# smart-car-main-board.net
KiCad netlist of a schematic drawn in EasyEDA Pro
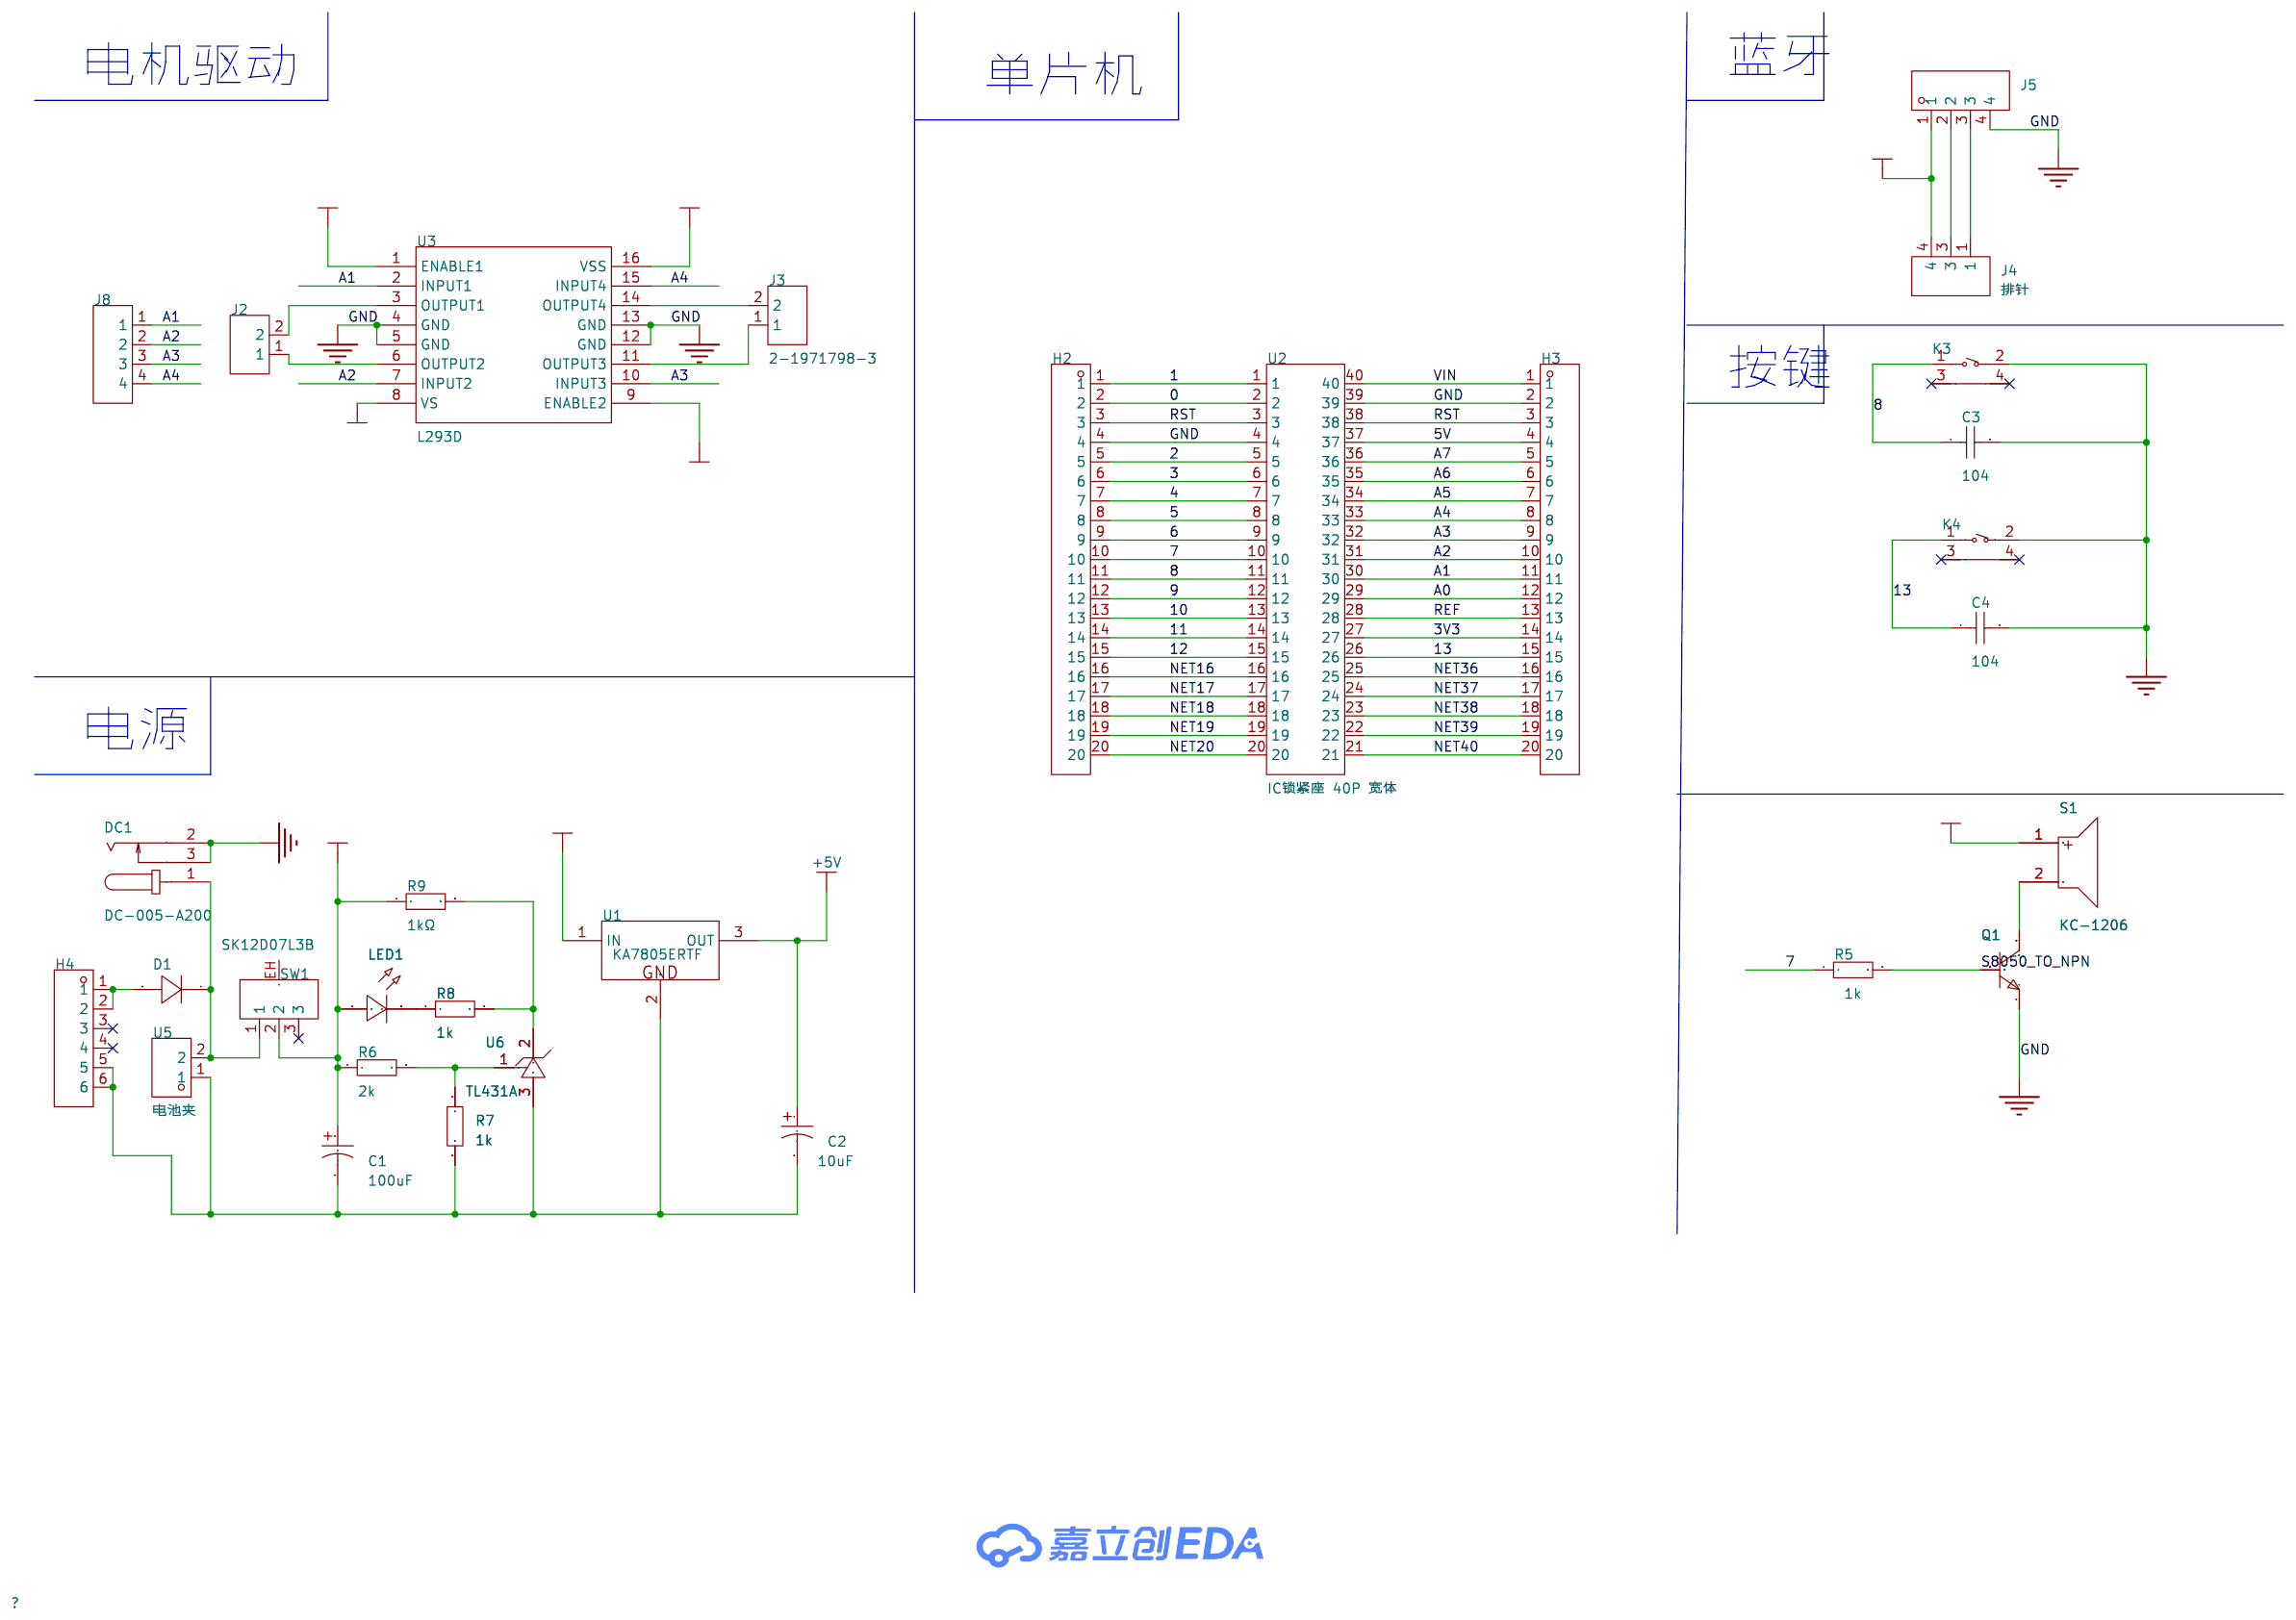
[diagram p0: schematic sheet]

(export (version "E")
  (design (tool "Eeschema 10.0.6"))
  (components
    (comp (ref "C1") (value "100uF") (libsource (lib "easyedapro") (part "CAP POL1")))
    (comp (ref "C2") (value "10uF") (libsource (lib "easyedapro") (part "CAP POL1")))
    (comp (ref "C3") (value "104") (libsource (lib "easyedapro") (part "CAP")))
    (comp (ref "C4") (value "104") (libsource (lib "easyedapro") (part "CAP")))
    (comp (ref "D1")
      (value "~")
      (footprint "easyedapro:DO_1N4007")
      (libsource (lib "easyedapro") (part "D_1N4007"))
    )
    (comp (ref "DC1")
      (value "DC-005-A200")
      (footprint "easyedapro:DC-IN-TH_DC-005-A200")
      (description "连接器类型:DC电源插座;安装方式:弯插;触点内径:2mm;触点外径:6.4mm;额定电流:3A;额定电压:30V;工作温度:-20°C~+70°C;")
      (fields (field (name "Manufacturer") "XUNPU(讯普)"))
      (libsource (lib "easyedapro") (part "DC-005-A200"))
    )
    (comp (ref "H2")
      (value "~")
      (footprint "easyedapro:HDR-TH_20P-P2.54-V-M-1")
      (libsource (lib "easyedapro") (part "HDR_2.54-1x20P"))
    )
    (comp (ref "H3")
      (value "~")
      (footprint "easyedapro:HDR-TH_20P-P2.54-V-M-1")
      (libsource (lib "easyedapro") (part "HDR_2.54-1x20P"))
    )
    (comp (ref "H4")
      (value "~")
      (footprint "easyedapro:HDR-TH_6P-P2.54-V-F")
      (libsource (lib "easyedapro") (part "Header-Female-2.54_1x6"))
    )
    (comp (ref "J2")
      (value "2-1971798-3")
      (footprint "easyedapro:CONN-TH_2-1971798-3")
      (libsource (lib "easyedapro") (part "2-1971798-3"))
    )
    (comp (ref "J3")
      (value "2-1971798-3")
      (footprint "easyedapro:CONN-TH_2-1971798-3")
      (libsource (lib "easyedapro") (part "2-1971798-3"))
    )
    (comp (ref "J4")
      (value "排针")
      (footprint "easyedapro:HDR-TH_3P-P2.54-V-M_H254-1X3P")
      (libsource (lib "easyedapro") (part "H254-1X4P-P2NC-PA4-PS5-PB8-L17MM"))
    )
    (comp (ref "J5")
      (value "~")
      (footprint "easyedapro:HDR-TH_4P-P2.54-V-F")
      (libsource (lib "easyedapro") (part "2.54-1*4P母"))
    )
    (comp (ref "J8")
      (value "~")
      (footprint "easyedapro:HDR-TH_4P-P2.54-V-M")
      (libsource (lib "easyedapro") (part "PZ254V-11-04P"))
    )
    (comp (ref "K3")
      (value "TC-6615-5-260G")
      (footprint "easyedapro:SW-TH_4P-L7.5-W5.0-P4.50")
      (fields (field (name "Manufacturer") "HCTL(华灿天禄)"))
      (libsource (lib "easyedapro") (part "TC-6615-5-260G"))
    )
    (comp (ref "K4")
      (value "TC-6615-5-260G")
      (footprint "easyedapro:SW-TH_4P-L7.5-W5.0-P4.50")
      (fields (field (name "Manufacturer") "HCTL(华灿天禄)"))
      (libsource (lib "easyedapro") (part "TC-6615-5-260G"))
    )
    (comp (ref "LED1")
      (value "~")
      (footprint "easyedapro:LED_TH-3mm")
      (libsource (lib "easyedapro") (part "LED_TH-R"))
    )
    (comp (ref "Q1")
      (value "~")
      (footprint "easyedapro:S8050_TO_92")
      (libsource (lib "easyedapro") (part "S8050_TO_NPN"))
    )
    (comp (ref "R5")
      (value "1k")
      (footprint "easyedapro:R_AXIAL-0.3")
      (libsource (lib "easyedapro") (part "电阻"))
    )
    (comp (ref "R6")
      (value "2k")
      (footprint "easyedapro:R_AXIAL-0.3")
      (libsource (lib "easyedapro") (part "电阻"))
    )
    (comp (ref "R7")
      (value "1k")
      (footprint "easyedapro:R_AXIAL-0.3")
      (libsource (lib "easyedapro") (part "电阻"))
    )
    (comp (ref "R8")
      (value "1k")
      (footprint "easyedapro:R_AXIAL-0.3")
      (libsource (lib "easyedapro") (part "电阻"))
    )
    (comp (ref "R9")
      (value "1kΩ")
      (footprint "easyedapro:R_AXIAL-0.3")
      (libsource (lib "easyedapro") (part "电阻"))
    )
    (comp (ref "S1")
      (value "KC-1206")
      (footprint "easyedapro:BUZ-TH_BD12.0-P6.50-D0.6-FD")
      (description "驱动方式:无源(外部驱动);构造类型:电磁式;频率:2.048kHz;声压(SPL):85dB;")
      (fields (field (name "Manufacturer Part") "KC1206 16Ω") (field (name "Manufacturer") "YUEXIN(悦馨)"))
      (libsource (lib "easyedapro") (part "KC1206 16Ω"))
    )
    (comp (ref "SW1")
      (value "SK12D07L3B")
      (footprint "easyedapro:SW-TH_SK-12D07-X-X")
      (description "电路结构:单刀双掷;安装方式:-;开关颜色:黑色;额定电流:300mA;额定电压:50V;工作寿命:1万次;")
      (fields (field (name "Manufacturer") "XKB Connection(中国星坤)"))
      (libsource (lib "easyedapro") (part "SK-12D07-L3-B"))
    )
    (comp (ref "U1")
      (value "KA7805ERTF")
      (footprint "easyedapro:TO-252-2_L6.6-W6.1-P4.58-LS9.7-BR")
      (description "输出类型:-;")
      (libsource (lib "easyedapro") (part "KA7805ERTF"))
    )
    (comp (ref "U2")
      (value "IC锁紧座 40P 宽体")
      (footprint "easyedapro:CONN-TH_40P-P2.54-V-R2-C20-S15.24-1")
      (libsource (lib "easyedapro") (part "IC锁紧座 40P 宽体"))
    )
    (comp (ref "U3")
      (value "L293D")
      (footprint "easyedapro:DIP-16_L20.0-W6.4-P2.54-LS7.6-BL")
      (description "具有二极管的推挽四通道驱动器")
      (fields (field (name "Manufacturer") "ST(意法半导体)"))
      (libsource (lib "easyedapro") (part "L293D"))
    )
    (comp (ref "U5")
      (value "电池夹")
      (footprint "easyedapro:CONN-TH_2P-P5.08_DB2EVC-5.08-2P-BK")
      (libsource (lib "easyedapro") (part "KF2EDGK-5.08-2P"))
    )
    (comp (ref "U6")
      (value "TL431A")
      (footprint "easyedapro:SOT-23-3_L2.9-W1.3-P1.90-LS2.4-BR")
      (description "输出类型:可调;工作电压:37V;输出电压:2.495V~36V;输出电流:100mA;精度:-;")
      (fields (field (name "Manufacturer") "PJSEMI(平晶微)"))
      (libsource (lib "easyedapro") (part "TL431A_C411753"))
    )
  )
  (nets
    (net (code "1") (name "+5") (class "Default")
      (node (ref "S1") (pin "1") (pinfunction "1_1") (pintype "unspecified"))
      (node (ref "U3") (pin "1") (pinfunction "ENABLE1_1") (pintype "unspecified"))
      (node (ref "U3") (pin "16") (pinfunction "VSS_16") (pintype "unspecified"))
      (node (ref "U3") (pin "9") (pinfunction "ENABLE2_9") (pintype "unspecified"))
    )
    (net (code "2") (name "+5V") (class "Default")
      (node (ref "C2") (pin "1") (pinfunction "1_1") (pintype "unspecified"))
      (node (ref "U1") (pin "3") (pinfunction "OUT_3") (pintype "unspecified"))
    )
    (net (code "3") (name "+VCC") (class "Default")
      (node (ref "C1") (pin "1") (pinfunction "1_1") (pintype "unspecified"))
      (node (ref "LED1") (pin "1") (pinfunction "C_1") (pintype "input"))
      (node (ref "R6") (pin "1") (pinfunction "1_1") (pintype "input"))
      (node (ref "R9") (pin "1") (pinfunction "1_1") (pintype "input"))
      (node (ref "SW1") (pin "2") (pinfunction "2_2") (pintype "unspecified"))
      (node (ref "U1") (pin "1") (pinfunction "IN_1") (pintype "unspecified"))
      (node (ref "U3") (pin "8") (pinfunction "VS_8") (pintype "unspecified"))
    )
    (net (code "4") (name "/0") (class "Default")
      (node (ref "H2") (pin "2") (pinfunction "2_2") (pintype "input"))
      (node (ref "U2") (pin "2") (pinfunction "2_2") (pintype "unspecified"))
    )
    (net (code "5") (name "/1") (class "Default")
      (node (ref "H2") (pin "1") (pinfunction "1_1") (pintype "input"))
      (node (ref "U2") (pin "1") (pinfunction "1_1") (pintype "unspecified"))
    )
    (net (code "6") (name "/2") (class "Default")
      (node (ref "H2") (pin "5") (pinfunction "5_5") (pintype "input"))
      (node (ref "U2") (pin "5") (pinfunction "5_5") (pintype "unspecified"))
    )
    (net (code "7") (name "/3") (class "Default")
      (node (ref "H2") (pin "6") (pinfunction "6_6") (pintype "input"))
      (node (ref "U2") (pin "6") (pinfunction "6_6") (pintype "unspecified"))
    )
    (net (code "8") (name "/4") (class "Default")
      (node (ref "H2") (pin "7") (pinfunction "7_7") (pintype "input"))
      (node (ref "U2") (pin "7") (pinfunction "7_7") (pintype "unspecified"))
    )
    (net (code "9") (name "/5") (class "Default")
      (node (ref "H2") (pin "8") (pinfunction "8_8") (pintype "input"))
      (node (ref "U2") (pin "8") (pinfunction "8_8") (pintype "unspecified"))
    )
    (net (code "10") (name "/5V") (class "Default")
      (node (ref "H3") (pin "4") (pinfunction "4_4") (pintype "input"))
      (node (ref "U2") (pin "37") (pinfunction "37_37") (pintype "unspecified"))
    )
    (net (code "11") (name "/6") (class "Default")
      (node (ref "H2") (pin "9") (pinfunction "9_9") (pintype "input"))
      (node (ref "U2") (pin "9") (pinfunction "9_9") (pintype "unspecified"))
    )
    (net (code "12") (name "/7") (class "Default")
      (node (ref "H2") (pin "10") (pinfunction "10_10") (pintype "input"))
      (node (ref "R5") (pin "1") (pinfunction "1_1") (pintype "input"))
      (node (ref "U2") (pin "10") (pinfunction "10_10") (pintype "unspecified"))
    )
    (net (code "13") (name "/8") (class "Default")
      (node (ref "C3") (pin "1") (pinfunction "1_1") (pintype "unspecified"))
      (node (ref "H2") (pin "11") (pinfunction "11_11") (pintype "input"))
      (node (ref "K3") (pin "1") (pinfunction "1_1") (pintype "unspecified"))
      (node (ref "U2") (pin "11") (pinfunction "11_11") (pintype "unspecified"))
    )
    (net (code "14") (name "/9") (class "Default")
      (node (ref "H2") (pin "12") (pinfunction "12_12") (pintype "input"))
      (node (ref "U2") (pin "12") (pinfunction "12_12") (pintype "unspecified"))
    )
    (net (code "15") (name "/10") (class "Default")
      (node (ref "H2") (pin "13") (pinfunction "13_13") (pintype "input"))
      (node (ref "U2") (pin "13") (pinfunction "13_13") (pintype "unspecified"))
    )
    (net (code "16") (name "/11") (class "Default")
      (node (ref "H2") (pin "14") (pinfunction "14_14") (pintype "input"))
      (node (ref "U2") (pin "14") (pinfunction "14_14") (pintype "unspecified"))
    )
    (net (code "17") (name "/12") (class "Default")
      (node (ref "H2") (pin "15") (pinfunction "15_15") (pintype "input"))
      (node (ref "U2") (pin "15") (pinfunction "15_15") (pintype "unspecified"))
    )
    (net (code "18") (name "/13") (class "Default")
      (node (ref "C4") (pin "1") (pinfunction "1_1") (pintype "unspecified"))
      (node (ref "H3") (pin "15") (pinfunction "15_15") (pintype "input"))
      (node (ref "K4") (pin "1") (pinfunction "1_1") (pintype "unspecified"))
      (node (ref "U2") (pin "26") (pinfunction "26_26") (pintype "unspecified"))
    )
    (net (code "19") (name "/A0") (class "Default")
      (node (ref "H3") (pin "12") (pinfunction "12_12") (pintype "input"))
      (node (ref "U2") (pin "29") (pinfunction "29_29") (pintype "unspecified"))
    )
    (net (code "20") (name "/A1") (class "Default")
      (node (ref "H3") (pin "11") (pinfunction "11_11") (pintype "input"))
      (node (ref "J8") (pin "1") (pinfunction "1_1") (pintype "unspecified"))
      (node (ref "U2") (pin "30") (pinfunction "30_30") (pintype "unspecified"))
      (node (ref "U3") (pin "2") (pinfunction "INPUT1_2") (pintype "unspecified"))
    )
    (net (code "21") (name "/A2") (class "Default")
      (node (ref "H3") (pin "10") (pinfunction "10_10") (pintype "input"))
      (node (ref "J8") (pin "2") (pinfunction "2_2") (pintype "unspecified"))
      (node (ref "U2") (pin "31") (pinfunction "31_31") (pintype "unspecified"))
      (node (ref "U3") (pin "7") (pinfunction "INPUT2_7") (pintype "unspecified"))
    )
    (net (code "22") (name "/A3") (class "Default")
      (node (ref "H3") (pin "9") (pinfunction "9_9") (pintype "input"))
      (node (ref "J8") (pin "3") (pinfunction "3_3") (pintype "unspecified"))
      (node (ref "U2") (pin "32") (pinfunction "32_32") (pintype "unspecified"))
      (node (ref "U3") (pin "10") (pinfunction "INPUT3_10") (pintype "unspecified"))
    )
    (net (code "23") (name "/A4") (class "Default")
      (node (ref "H3") (pin "8") (pinfunction "8_8") (pintype "input"))
      (node (ref "J8") (pin "4") (pinfunction "4_4") (pintype "unspecified"))
      (node (ref "U2") (pin "33") (pinfunction "33_33") (pintype "unspecified"))
      (node (ref "U3") (pin "15") (pinfunction "INPUT4_15") (pintype "unspecified"))
    )
    (net (code "24") (name "/A5") (class "Default")
      (node (ref "H3") (pin "7") (pinfunction "7_7") (pintype "input"))
      (node (ref "U2") (pin "34") (pinfunction "34_34") (pintype "unspecified"))
    )
    (net (code "25") (name "/A6") (class "Default")
      (node (ref "H3") (pin "6") (pinfunction "6_6") (pintype "input"))
      (node (ref "U2") (pin "35") (pinfunction "35_35") (pintype "unspecified"))
    )
    (net (code "26") (name "/A7") (class "Default")
      (node (ref "H3") (pin "5") (pinfunction "5_5") (pintype "input"))
      (node (ref "U2") (pin "36") (pinfunction "36_36") (pintype "unspecified"))
    )
    (net (code "27") (name "/NET16") (class "Default")
      (node (ref "H2") (pin "16") (pinfunction "16_16") (pintype "input"))
      (node (ref "U2") (pin "16") (pinfunction "16_16") (pintype "unspecified"))
    )
    (net (code "28") (name "/NET17") (class "Default")
      (node (ref "H2") (pin "17") (pinfunction "17_17") (pintype "input"))
      (node (ref "U2") (pin "17") (pinfunction "17_17") (pintype "unspecified"))
    )
    (net (code "29") (name "/NET18") (class "Default")
      (node (ref "H2") (pin "18") (pinfunction "18_18") (pintype "input"))
      (node (ref "U2") (pin "18") (pinfunction "18_18") (pintype "unspecified"))
    )
    (net (code "30") (name "/NET19") (class "Default")
      (node (ref "H2") (pin "19") (pinfunction "19_19") (pintype "input"))
      (node (ref "U2") (pin "19") (pinfunction "19_19") (pintype "unspecified"))
    )
    (net (code "31") (name "/NET20") (class "Default")
      (node (ref "H2") (pin "20") (pinfunction "20_20") (pintype "input"))
      (node (ref "U2") (pin "20") (pinfunction "20_20") (pintype "unspecified"))
    )
    (net (code "32") (name "/NET36") (class "Default")
      (node (ref "H3") (pin "16") (pinfunction "16_16") (pintype "input"))
      (node (ref "U2") (pin "25") (pinfunction "25_25") (pintype "unspecified"))
    )
    (net (code "33") (name "/NET37") (class "Default")
      (node (ref "H3") (pin "17") (pinfunction "17_17") (pintype "input"))
      (node (ref "U2") (pin "24") (pinfunction "24_24") (pintype "unspecified"))
    )
    (net (code "34") (name "/NET38") (class "Default")
      (node (ref "H3") (pin "18") (pinfunction "18_18") (pintype "input"))
      (node (ref "U2") (pin "23") (pinfunction "23_23") (pintype "unspecified"))
    )
    (net (code "35") (name "/NET39") (class "Default")
      (node (ref "H3") (pin "19") (pinfunction "19_19") (pintype "input"))
      (node (ref "U2") (pin "22") (pinfunction "22_22") (pintype "unspecified"))
    )
    (net (code "36") (name "/NET40") (class "Default")
      (node (ref "H3") (pin "20") (pinfunction "20_20") (pintype "input"))
      (node (ref "U2") (pin "21") (pinfunction "21_21") (pintype "unspecified"))
    )
    (net (code "37") (name "/REF") (class "Default")
      (node (ref "H3") (pin "13") (pinfunction "13_13") (pintype "input"))
      (node (ref "U2") (pin "28") (pinfunction "28_28") (pintype "unspecified"))
    )
    (net (code "38") (name "/RST") (class "Default")
      (node (ref "H2") (pin "3") (pinfunction "3_3") (pintype "input"))
      (node (ref "H3") (pin "3") (pinfunction "3_3") (pintype "input"))
      (node (ref "U2") (pin "3") (pinfunction "3_3") (pintype "unspecified"))
      (node (ref "U2") (pin "38") (pinfunction "38_38") (pintype "unspecified"))
    )
    (net (code "39") (name "/S8050_TO_NPN") (class "Default")
      (node (ref "Q1") (pin "2") (pinfunction "B_2") (pintype "unspecified"))
      (node (ref "R5") (pin "2") (pinfunction "2_2") (pintype "input"))
    )
    (net (code "40") (name "/VIN") (class "Default")
      (node (ref "H3") (pin "1") (pinfunction "1_1") (pintype "input"))
      (node (ref "U2") (pin "40") (pinfunction "40_40") (pintype "unspecified"))
    )
    (net (code "41") (name "3V3") (class "Default")
      (node (ref "H3") (pin "14") (pinfunction "14_14") (pintype "input"))
      (node (ref "J4") (pin "4") (pinfunction "4_4") (pintype "unspecified"))
      (node (ref "J5") (pin "1") (pinfunction "1_1") (pintype "unspecified"))
      (node (ref "U2") (pin "27") (pinfunction "27_27") (pintype "unspecified"))
    )
    (net (code "42") (name "GND") (class "Default")
      (node (ref "C3") (pin "2") (pinfunction "2_2") (pintype "unspecified"))
      (node (ref "C4") (pin "2") (pinfunction "2_2") (pintype "unspecified"))
      (node (ref "DC1") (pin "2") (pinfunction "2_2") (pintype "unspecified"))
      (node (ref "DC1") (pin "3") (pinfunction "3_3") (pintype "unspecified"))
      (node (ref "H2") (pin "4") (pinfunction "4_4") (pintype "input"))
      (node (ref "H3") (pin "2") (pinfunction "2_2") (pintype "input"))
      (node (ref "J5") (pin "4") (pinfunction "4_4") (pintype "unspecified"))
      (node (ref "K3") (pin "2") (pinfunction "2_2") (pintype "unspecified"))
      (node (ref "K4") (pin "2") (pinfunction "2_2") (pintype "unspecified"))
      (node (ref "Q1") (pin "1") (pinfunction "E_1") (pintype "unspecified"))
      (node (ref "U2") (pin "39") (pinfunction "39_39") (pintype "unspecified"))
      (node (ref "U2") (pin "4") (pinfunction "4_4") (pintype "unspecified"))
      (node (ref "U3") (pin "12") (pinfunction "GND_12") (pintype "unspecified"))
      (node (ref "U3") (pin "13") (pinfunction "GND_13") (pintype "unspecified"))
      (node (ref "U3") (pin "4") (pinfunction "GND_4") (pintype "unspecified"))
      (node (ref "U3") (pin "5") (pinfunction "GND_5") (pintype "unspecified"))
    )
    (net (code "43") (name "Net-(D1-A)") (class "Default")
      (node (ref "D1") (pin "2") (pinfunction "A_2") (pintype "input"))
      (node (ref "H4") (pin "1") (pinfunction "1_1") (pintype "unspecified"))
      (node (ref "H4") (pin "2") (pinfunction "2_2") (pintype "unspecified"))
    )
    (net (code "44") (name "Net-(D1-K)") (class "Default")
      (node (ref "D1") (pin "1") (pinfunction "K_1") (pintype "input"))
      (node (ref "DC1") (pin "1") (pinfunction "1_1") (pintype "unspecified"))
      (node (ref "SW1") (pin "1") (pinfunction "1_1") (pintype "unspecified"))
      (node (ref "U5") (pin "2") (pinfunction "2_2") (pintype "unspecified"))
    )
    (net (code "45") (name "Net-(J4-Pad1)") (class "Default")
      (node (ref "J4") (pin "1") (pinfunction "1_1") (pintype "unspecified"))
      (node (ref "J5") (pin "3") (pinfunction "3_3") (pintype "unspecified"))
    )
    (net (code "46") (name "Net-(J4-Pad3)") (class "Default")
      (node (ref "J4") (pin "3") (pinfunction "3_3") (pintype "unspecified"))
      (node (ref "J5") (pin "2") (pinfunction "2_2") (pintype "unspecified"))
    )
    (net (code "47") (name "Net-(LED1-A)") (class "Default")
      (node (ref "LED1") (pin "2") (pinfunction "A_2") (pintype "input"))
      (node (ref "R8") (pin "1") (pinfunction "1_1") (pintype "input"))
    )
    (net (code "48") (name "Net-(Q1-C)") (class "Default")
      (node (ref "Q1") (pin "3") (pinfunction "C_3") (pintype "unspecified"))
      (node (ref "S1") (pin "2") (pinfunction "2_2") (pintype "unspecified"))
    )
    (net (code "49") (name "Net-(U1-GND)") (class "Default")
      (node (ref "C1") (pin "2") (pinfunction "2_2") (pintype "unspecified"))
      (node (ref "C2") (pin "2") (pinfunction "2_2") (pintype "unspecified"))
      (node (ref "H4") (pin "5") (pinfunction "5_5") (pintype "unspecified"))
      (node (ref "H4") (pin "6") (pinfunction "6_6") (pintype "unspecified"))
      (node (ref "R7") (pin "1") (pinfunction "1_1") (pintype "input"))
      (node (ref "U1") (pin "2") (pinfunction "GND_2") (pintype "unspecified"))
      (node (ref "U5") (pin "1") (pinfunction "1_1") (pintype "unspecified"))
      (node (ref "U6") (pin "3") (pinfunction "A_3") (pintype "unspecified"))
    )
    (net (code "50") (name "Net-(U3-OUTPUT1)") (class "Default")
      (node (ref "J2") (pin "2") (pinfunction "2_2") (pintype "unspecified"))
      (node (ref "U3") (pin "3") (pinfunction "OUTPUT1_3") (pintype "unspecified"))
    )
    (net (code "51") (name "Net-(U3-OUTPUT2)") (class "Default")
      (node (ref "J2") (pin "1") (pinfunction "1_1") (pintype "unspecified"))
      (node (ref "U3") (pin "6") (pinfunction "OUTPUT2_6") (pintype "unspecified"))
    )
    (net (code "52") (name "Net-(U3-OUTPUT3)") (class "Default")
      (node (ref "J3") (pin "1") (pinfunction "1_1") (pintype "unspecified"))
      (node (ref "U3") (pin "11") (pinfunction "OUTPUT3_11") (pintype "unspecified"))
    )
    (net (code "53") (name "Net-(U3-OUTPUT4)") (class "Default")
      (node (ref "J3") (pin "2") (pinfunction "2_2") (pintype "unspecified"))
      (node (ref "U3") (pin "14") (pinfunction "OUTPUT4_14") (pintype "unspecified"))
    )
    (net (code "54") (name "Net-(U6-K)") (class "Default")
      (node (ref "R8") (pin "2") (pinfunction "2_2") (pintype "input"))
      (node (ref "R9") (pin "2") (pinfunction "2_2") (pintype "input"))
      (node (ref "U6") (pin "2") (pinfunction "K_2") (pintype "unspecified"))
    )
    (net (code "55") (name "Net-(U6-R)") (class "Default")
      (node (ref "R6") (pin "2") (pinfunction "2_2") (pintype "input"))
      (node (ref "R7") (pin "2") (pinfunction "2_2") (pintype "input"))
      (node (ref "U6") (pin "1") (pinfunction "R_1") (pintype "unspecified"))
    )
    (net (code "56") (name "unconnected-(H4-Pad3)") (class "Default")
      (node (ref "H4") (pin "3") (pinfunction "3_3") (pintype "unspecified+no_connect"))
    )
    (net (code "57") (name "unconnected-(H4-Pad4)") (class "Default")
      (node (ref "H4") (pin "4") (pinfunction "4_4") (pintype "unspecified+no_connect"))
    )
    (net (code "58") (name "unconnected-(K3-Pad3)") (class "Default")
      (node (ref "K3") (pin "3") (pinfunction "3_3") (pintype "unspecified+no_connect"))
    )
    (net (code "59") (name "unconnected-(K3-Pad4)") (class "Default")
      (node (ref "K3") (pin "4") (pinfunction "4_4") (pintype "unspecified+no_connect"))
    )
    (net (code "60") (name "unconnected-(K4-Pad3)") (class "Default")
      (node (ref "K4") (pin "3") (pinfunction "3_3") (pintype "unspecified+no_connect"))
    )
    (net (code "61") (name "unconnected-(K4-Pad4)") (class "Default")
      (node (ref "K4") (pin "4") (pinfunction "4_4") (pintype "unspecified+no_connect"))
    )
    (net (code "62") (name "unconnected-(SW1-Pad3)") (class "Default")
      (node (ref "SW1") (pin "3") (pinfunction "3_3") (pintype "unspecified+no_connect"))
    )
    (net (code "63") (name "unconnected-(SW1-PadEH)") (class "Default")
      (node (ref "SW1") (pin "EH") (pinfunction "EH_EH") (pintype "unspecified"))
    )
  )
)
